# Current_Monitor.net
KiCad netlist of a schematic drawn in Altium Designer
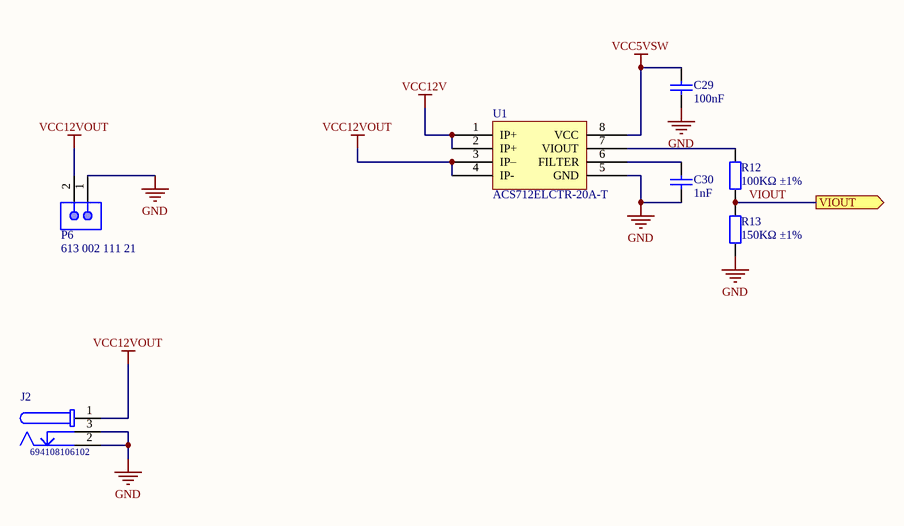
[diagram p0: Current Monitor.SchDoc]

(export (version "E")
  (design (tool "Eeschema 10.0.6"))
  (components
    (comp (ref "C29")
      (value "100nF")
      (footprint "0402_C")
      (description "Chip capacitors")
      (fields
        (field (name "MANUFACTURER") "Samsung Electro-Mechanics")
        (field (name "PARTNUMBER") "CL05B104KO5NNNC")
      )
      (libsource (lib "Miscellaneous Devices LC") (part "0402 100nF (104) 10% 16V"))
    )
    (comp (ref "C30")
      (value "1nF")
      (footprint "0402_C")
      (description "Chip capacitor")
      (fields
        (field (name "MANUFACTURER") "Guangdong Fenghua Advanced Tech")
        (field (name "PARTNUMBER") "0402B102K500NT")
      )
      (libsource (lib "Miscellaneous Devices LC") (part "0402 1nF (102) 10% 50V"))
    )
    (comp (ref "J2")
      (value "694108106102")
      (footprint "694108106102")
      (description "DC Power Jack Connector with 4 soldering pads & Pegs WR-DC, Male, Right Angled, SMT, 5 A, 24 V")
      (fields (field (name "MANUFACTURER") "Wurth Elektronik") (field (name "PUBLISHER") "WurthElektronik"))
      (libsource (lib "Altium Content Vault") (part "WE-JACK-2CD3-RN"))
    )
    (comp (ref "P6")
      (value "613 002 111 21")
      (footprint "WE-61300211121_V")
      (libsource (lib "Altium Content Vault") (part "CN-1P-M-R2"))
    )
    (comp (ref "R12")
      (value "100KΩ ±1%")
      (footprint "0402_R")
      (description "Chip resistor")
      (fields (field (name "MANUFACTURER") "Uniroyal Elec") (field (name "PARTNUMBER") "0402WGF1003TCE"))
      (libsource (lib "Miscellaneous Devices LC") (part "0402 100K (1003) 1%"))
    )
    (comp (ref "R13")
      (value "150KΩ ±1%")
      (footprint "0402_R")
      (description "Chip resistor")
      (fields (field (name "MANUFACTURER") "Uniroyal Elec") (field (name "PARTNUMBER") "0402WGF1503TCE"))
      (libsource (lib "Miscellaneous Devices LC") (part "0402 150K (1503) 1%"))
    )
    (comp (ref "U1")
      (value "ACS712ELCTR-20A-T")
      (footprint "SOIC-8_150mil")
      (description "传感器")
      (libsource (lib "Miscellaneous Devices LC") (part "ACS712ELCTR-20A-T_[C10681]"))
    )
  )
  (nets
    (net (code "1") (name "/VIOUT") (class "Default")
      (node (ref "R12") (pin "1") (pinfunction "1_1") (pintype "passive"))
      (node (ref "R13") (pin "2") (pinfunction "2_2") (pintype "passive"))
    )
    (net (code "2") (name "GND") (class "Default")
      (node (ref "C29") (pin "1") (pinfunction "1_1") (pintype "passive"))
      (node (ref "C30") (pin "1") (pinfunction "1_1") (pintype "passive"))
      (node (ref "J2") (pin "2") (pinfunction "2_2") (pintype "passive"))
      (node (ref "J2") (pin "3") (pinfunction "3_3") (pintype "passive"))
      (node (ref "P6") (pin "1") (pinfunction "1_1") (pintype "passive"))
      (node (ref "R13") (pin "1") (pinfunction "1_1") (pintype "passive"))
      (node (ref "U1") (pin "5") (pinfunction "GND_5") (pintype "passive"))
    )
    (net (code "3") (name "Net-(U1-FILTER)") (class "Default")
      (node (ref "C30") (pin "2") (pinfunction "2_2") (pintype "passive"))
      (node (ref "U1") (pin "6") (pinfunction "FILTER_6") (pintype "passive"))
    )
    (net (code "4") (name "Net-(U1-VIOUT)") (class "Default")
      (node (ref "R12") (pin "2") (pinfunction "2_2") (pintype "passive"))
      (node (ref "U1") (pin "7") (pinfunction "VIOUT_7") (pintype "passive"))
    )
    (net (code "5") (name "VCC5VSW") (class "Default")
      (node (ref "C29") (pin "2") (pinfunction "2_2") (pintype "passive"))
      (node (ref "U1") (pin "8") (pinfunction "VCC_8") (pintype "passive"))
    )
    (net (code "6") (name "VCC12V") (class "Default")
      (node (ref "U1") (pin "1") (pinfunction "IP+_1") (pintype "passive"))
      (node (ref "U1") (pin "2") (pinfunction "IP+_2") (pintype "passive"))
    )
    (net (code "7") (name "VCC12VOUT") (class "Default")
      (node (ref "J2") (pin "1") (pinfunction "1_1") (pintype "passive"))
      (node (ref "P6") (pin "2") (pinfunction "2_2") (pintype "passive"))
      (node (ref "U1") (pin "3") (pinfunction "IP–_3") (pintype "passive"))
      (node (ref "U1") (pin "4") (pinfunction "IP-_4") (pintype "passive"))
    )
  )
)
